# Logic_DC_Jack_v1_0.net
KiCad netlist of a schematic drawn in EAGLE
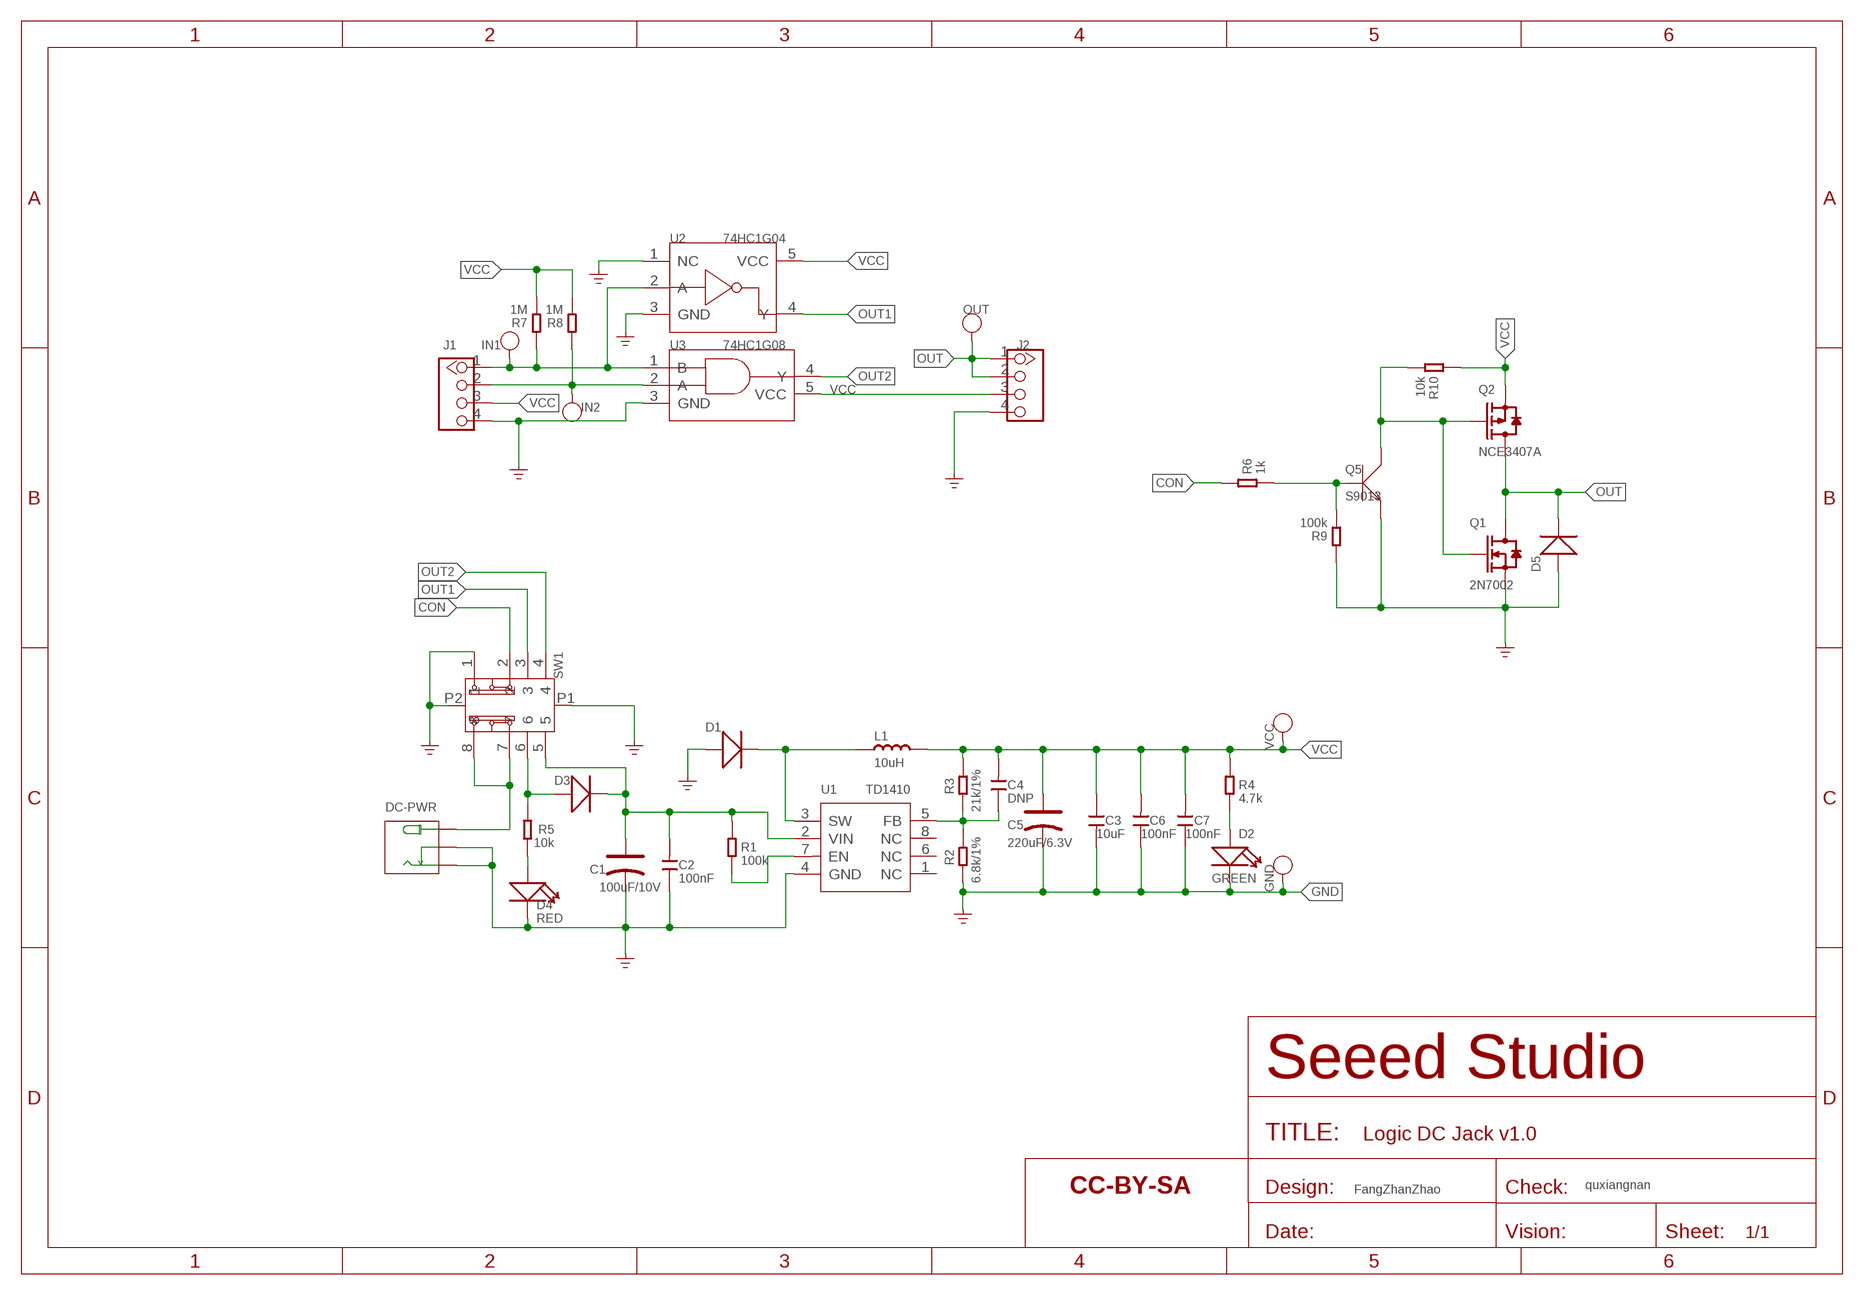
[diagram p0: schematic, sheet 1]

(export (version "E")
  (design (tool "Eeschema 10.0.6"))
  (components
    (comp (ref "C1")
      (value "100uF/10V")
      (footprint "eagle-import:AVX-B")
      (libsource (lib "eagle-import") (part "CAP-POLAR-AVX-B"))
    )
    (comp (ref "C2")
      (value "100nF")
      (footprint "eagle-import:C0603")
      (libsource (lib "eagle-import") (part "CAP-0603"))
    )
    (comp (ref "C3")
      (value "10uF")
      (footprint "eagle-import:C0805")
      (libsource (lib "eagle-import") (part "CAP-0805"))
    )
    (comp (ref "C4")
      (value "DNP")
      (footprint "eagle-import:C0603")
      (libsource (lib "eagle-import") (part "CAP-0603"))
    )
    (comp (ref "C5")
      (value "220uF/6.3V")
      (footprint "eagle-import:AVX-B")
      (libsource (lib "eagle-import") (part "CAP-POLAR-AVX-B"))
    )
    (comp (ref "C6")
      (value "100nF")
      (footprint "eagle-import:C0603")
      (libsource (lib "eagle-import") (part "CAP-0603"))
    )
    (comp (ref "C7")
      (value "100nF")
      (footprint "eagle-import:C0603")
      (libsource (lib "eagle-import") (part "CAP-0603"))
    )
    (comp (ref "D1")
      (value "DIODE'SMA'")
      (footprint "eagle-import:DO-214AC")
      (libsource (lib "eagle-import") (part "DIODE'SMA'"))
    )
    (comp (ref "D2")
      (value "GREEN")
      (footprint "eagle-import:LED-0603")
      (libsource (lib "eagle-import") (part "LED'0603'"))
    )
    (comp (ref "D3")
      (value "304020009")
      (footprint "eagle-import:DO-214AC")
      (libsource (lib "eagle-import") (part "DIODE'SMA'"))
    )
    (comp (ref "D4")
      (value "RED")
      (footprint "eagle-import:LED-0603")
      (libsource (lib "eagle-import") (part "LED'0603'"))
    )
    (comp (ref "D5")
      (value "DIODE'1206'")
      (footprint "eagle-import:SOD-123")
      (libsource (lib "eagle-import") (part "DIODE'1206'"))
    )
    (comp (ref "DC-PWR")
      (value "320120002")
      (footprint "eagle-import:3P-L11.6_W9.6_H7.0MM")
      (libsource (lib "eagle-import") (part "POWER-JACK-DC'DC-044'"))
    )
    (comp (ref "GND")
      (value "PAD-TEST-POINT'4545'")
      (footprint "eagle-import:TP-D45MIL")
      (fields (field (name "PARTNO") "DNP"))
      (libsource (lib "eagle-import") (part "PAD-TEST-POINT'4545'"))
    )
    (comp (ref "IN1")
      (value "PAD-TEST-POINT'4545'")
      (footprint "eagle-import:TP-D45MIL")
      (fields (field (name "PARTNO") "DNP"))
      (libsource (lib "eagle-import") (part "PAD-TEST-POINT'4545'"))
    )
    (comp (ref "IN2")
      (value "PAD-TEST-POINT'4545'")
      (footprint "eagle-import:TP-D45MIL")
      (fields (field (name "PARTNO") "DNP"))
      (libsource (lib "eagle-import") (part "PAD-TEST-POINT'4545'"))
    )
    (comp (ref "J1")
      (value "GROVE-CONNECTOR-DIP-2.0")
      (footprint "eagle-import:4P-2.0")
      (libsource (lib "eagle-import") (part "GROVE-CONNECTOR-DIP-2.0"))
    )
    (comp (ref "J2")
      (value "GROVE-CONNECTOR-DIP-2.0")
      (footprint "eagle-import:4P-2.0")
      (libsource (lib "eagle-import") (part "GROVE-CONNECTOR-DIP-2.0"))
    )
    (comp (ref "L1")
      (value "10uH")
      (footprint "eagle-import:L0630")
      (libsource (lib "eagle-import") (part "INDUCTOR/FERRITE-BEAD'0630'"))
    )
    (comp (ref "OUT")
      (value "PAD-TEST-POINT'4545'")
      (footprint "eagle-import:TP-D45MIL")
      (fields (field (name "PARTNO") "DNP"))
      (libsource (lib "eagle-import") (part "PAD-TEST-POINT'4545'"))
    )
    (comp (ref "Q1")
      (value "2N7002")
      (footprint "eagle-import:SOT-23")
      (libsource (lib "eagle-import") (part "MOSFET-N'SOT23'"))
    )
    (comp (ref "Q2")
      (value "NCE3407A")
      (footprint "eagle-import:SOT-23")
      (libsource (lib "eagle-import") (part "MOSFET-P'SI2323CDS/SI2305DS{lt}BR{gt}'"))
    )
    (comp (ref "Q5")
      (value "S9013")
      (footprint "eagle-import:SOT-23")
      (libsource (lib "eagle-import") (part "TRANSISTOR-NPN-SOT23"))
    )
    (comp (ref "R1")
      (value "100k")
      (footprint "eagle-import:R0603")
      (libsource (lib "eagle-import") (part "RES-0603"))
    )
    (comp (ref "R2")
      (value "6.8k/1%")
      (footprint "eagle-import:R0603")
      (libsource (lib "eagle-import") (part "RES-0603"))
    )
    (comp (ref "R3")
      (value "21k/1%")
      (footprint "eagle-import:R0603")
      (libsource (lib "eagle-import") (part "RES-0603"))
    )
    (comp (ref "R4")
      (value "4.7k")
      (footprint "eagle-import:R0603")
      (libsource (lib "eagle-import") (part "RES-0603"))
    )
    (comp (ref "R5")
      (value "10k")
      (footprint "eagle-import:R0603")
      (libsource (lib "eagle-import") (part "RES-0603"))
    )
    (comp (ref "R6")
      (value "1k")
      (footprint "eagle-import:R0603")
      (libsource (lib "eagle-import") (part "RES-0603"))
    )
    (comp (ref "R7")
      (value "1M")
      (footprint "eagle-import:R0603")
      (libsource (lib "eagle-import") (part "RES-0603"))
    )
    (comp (ref "R8")
      (value "1M")
      (footprint "eagle-import:R0603")
      (libsource (lib "eagle-import") (part "RES-0603"))
    )
    (comp (ref "R9")
      (value "100k")
      (footprint "eagle-import:R0603")
      (libsource (lib "eagle-import") (part "RES-0603"))
    )
    (comp (ref "R10")
      (value "10k")
      (footprint "eagle-import:R0603")
      (libsource (lib "eagle-import") (part "RES-0603"))
    )
    (comp (ref "SW1")
      (value "SWITCH-SK-23D07SK-22D03H-G4")
      (footprint "eagle-import:8P-3CH-L16_W6.5_H7.5MM-90D")
      (libsource (lib "eagle-import") (part "SWITCH-SK-23D07SK-22D03H-G4"))
    )
    (comp (ref "U$12")
      (value "SEEEDSTUDIO-OPEN-SCH-FRAME")
      (footprint "eagle-import:SEEEDSTUDIO-PCB-FRAME")
      (libsource (lib "eagle-import") (part "SEEEDSTUDIO-OPEN-SCH-FRAME"))
    )
    (comp (ref "U1")
      (value "TD1410")
      (footprint "eagle-import:SOP-8")
      (libsource (lib "eagle-import") (part "PMIC-TD1410"))
    )
    (comp (ref "U2")
      (value "74HC1G04")
      (footprint "eagle-import:SOT-353")
      (libsource (lib "eagle-import") (part "74HC1G04'GW'"))
    )
    (comp (ref "U3")
      (value "74HC1G08")
      (footprint "eagle-import:SOT-353")
      (libsource (lib "eagle-import") (part "74HC1G08'GW'"))
    )
    (comp (ref "VCC")
      (value "PAD-TEST-POINT'4545'")
      (footprint "eagle-import:TP-D45MIL")
      (fields (field (name "PARTNO") "DNP"))
      (libsource (lib "eagle-import") (part "PAD-TEST-POINT'4545'"))
    )
  )
  (nets
    (net (code "1") (name "CON") (class "Default")
      (node (ref "R6") (pin "2") (pinfunction "2_2") (pintype "passive"))
      (node (ref "SW1") (pin "2") (pinfunction "2_2") (pintype "bidirectional"))
    )
    (net (code "2") (name "GND") (class "Default")
      (node (ref "C1") (pin "-") (pinfunction "-_-") (pintype "passive"))
      (node (ref "C2") (pin "1") (pinfunction "1_1") (pintype "passive"))
      (node (ref "C3") (pin "2") (pinfunction "2_2") (pintype "passive"))
      (node (ref "C5") (pin "-") (pinfunction "-_-") (pintype "passive"))
      (node (ref "C6") (pin "1") (pinfunction "1_1") (pintype "passive"))
      (node (ref "C7") (pin "1") (pinfunction "1_1") (pintype "passive"))
      (node (ref "D1") (pin "1") (pinfunction "+_1") (pintype "passive"))
      (node (ref "D2") (pin "-") (pinfunction "-_-") (pintype "passive"))
      (node (ref "D4") (pin "-") (pinfunction "-_-") (pintype "passive"))
      (node (ref "D5") (pin "+") (pinfunction "+_+") (pintype "passive"))
      (node (ref "DC-PWR") (pin "-") (pinfunction "-_-") (pintype "bidirectional"))
      (node (ref "DC-PWR") (pin "CDN") (pinfunction "CDN_CDN") (pintype "bidirectional"))
      (node (ref "GND") (pin "T") (pinfunction "T_T") (pintype "bidirectional"))
      (node (ref "J1") (pin "4") (pinfunction "4_4") (pintype "bidirectional"))
      (node (ref "J2") (pin "4") (pinfunction "4_4") (pintype "bidirectional"))
      (node (ref "Q1") (pin "2") (pinfunction "S_2") (pintype "passive"))
      (node (ref "Q5") (pin "2") (pinfunction "E_2") (pintype "passive"))
      (node (ref "R2") (pin "1") (pinfunction "1_1") (pintype "passive"))
      (node (ref "R9") (pin "2") (pinfunction "2_2") (pintype "passive"))
      (node (ref "SW1") (pin "1") (pinfunction "1_1") (pintype "bidirectional"))
      (node (ref "SW1") (pin "P1") (pinfunction "P$1_P1") (pintype "bidirectional"))
      (node (ref "SW1") (pin "P2") (pinfunction "P$2_P2") (pintype "bidirectional"))
      (node (ref "U1") (pin "4") (pinfunction "GND_4") (pintype "power_in"))
      (node (ref "U2") (pin "1") (pinfunction "NC_1") (pintype "bidirectional"))
      (node (ref "U2") (pin "3") (pinfunction "GND_3") (pintype "power_in"))
      (node (ref "U3") (pin "3") (pinfunction "GND_3") (pintype "bidirectional"))
    )
    (net (code "3") (name "Net-(D1--)") (class "Default")
      (node (ref "D1") (pin "2") (pinfunction "-_2") (pintype "passive"))
      (node (ref "L1") (pin "1") (pinfunction "1_1") (pintype "passive"))
      (node (ref "U1") (pin "3") (pinfunction "SW_3") (pintype "output"))
    )
    (net (code "4") (name "Net-(D2-Pad+)") (class "Default")
      (node (ref "D2") (pin "+") (pinfunction "+_+") (pintype "passive"))
      (node (ref "R4") (pin "1") (pinfunction "1_1") (pintype "passive"))
    )
    (net (code "5") (name "Net-(D3-+)") (class "Default")
      (node (ref "D3") (pin "1") (pinfunction "+_1") (pintype "passive"))
      (node (ref "R5") (pin "2") (pinfunction "2_2") (pintype "passive"))
      (node (ref "SW1") (pin "6") (pinfunction "6_6") (pintype "bidirectional"))
    )
    (net (code "6") (name "Net-(D3--)") (class "Default")
      (node (ref "C1") (pin "+") (pinfunction "+_+") (pintype "passive"))
      (node (ref "C2") (pin "2") (pinfunction "2_2") (pintype "passive"))
      (node (ref "D3") (pin "2") (pinfunction "-_2") (pintype "passive"))
      (node (ref "R1") (pin "2") (pinfunction "2_2") (pintype "passive"))
      (node (ref "SW1") (pin "5") (pinfunction "5_5") (pintype "bidirectional"))
      (node (ref "U1") (pin "2") (pinfunction "VIN_2") (pintype "input"))
    )
    (net (code "7") (name "Net-(D4-Pad+)") (class "Default")
      (node (ref "D4") (pin "+") (pinfunction "+_+") (pintype "passive"))
      (node (ref "R5") (pin "1") (pinfunction "1_1") (pintype "passive"))
    )
    (net (code "8") (name "Net-(DC-PWR-Pad+)") (class "Default")
      (node (ref "DC-PWR") (pin "+") (pinfunction "+_+") (pintype "bidirectional"))
      (node (ref "SW1") (pin "7") (pinfunction "7_7") (pintype "bidirectional"))
      (node (ref "SW1") (pin "8") (pinfunction "8_8") (pintype "bidirectional"))
    )
    (net (code "9") (name "Net-(Q1-G)") (class "Default")
      (node (ref "Q1") (pin "1") (pinfunction "G_1") (pintype "passive"))
      (node (ref "Q2") (pin "1") (pinfunction "G_1") (pintype "passive"))
      (node (ref "Q5") (pin "3") (pinfunction "C_3") (pintype "passive"))
      (node (ref "R10") (pin "1") (pinfunction "1_1") (pintype "passive"))
    )
    (net (code "10") (name "Net-(Q5-B)") (class "Default")
      (node (ref "Q5") (pin "1") (pinfunction "B_1") (pintype "passive"))
      (node (ref "R6") (pin "1") (pinfunction "1_1") (pintype "passive"))
      (node (ref "R9") (pin "1") (pinfunction "1_1") (pintype "passive"))
    )
    (net (code "11") (name "Net-(U1-EN)") (class "Default")
      (node (ref "R1") (pin "1") (pinfunction "1_1") (pintype "passive"))
      (node (ref "U1") (pin "7") (pinfunction "EN_7") (pintype "input"))
    )
    (net (code "12") (name "Net-(U1-FB)") (class "Default")
      (node (ref "C4") (pin "1") (pinfunction "1_1") (pintype "passive"))
      (node (ref "R2") (pin "2") (pinfunction "2_2") (pintype "passive"))
      (node (ref "R3") (pin "2") (pinfunction "2_2") (pintype "passive"))
      (node (ref "U1") (pin "5") (pinfunction "FB_5") (pintype "input"))
    )
    (net (code "13") (name "Net-(U2-A)") (class "Default")
      (node (ref "IN1") (pin "T") (pinfunction "T_T") (pintype "bidirectional"))
      (node (ref "J1") (pin "1") (pinfunction "1_1") (pintype "bidirectional"))
      (node (ref "R7") (pin "2") (pinfunction "2_2") (pintype "passive"))
      (node (ref "U2") (pin "2") (pinfunction "A_2") (pintype "bidirectional"))
      (node (ref "U3") (pin "1") (pinfunction "B_1") (pintype "bidirectional"))
    )
    (net (code "14") (name "Net-(U3-A)") (class "Default")
      (node (ref "IN2") (pin "T") (pinfunction "T_T") (pintype "bidirectional"))
      (node (ref "J1") (pin "2") (pinfunction "2_2") (pintype "bidirectional"))
      (node (ref "R8") (pin "2") (pinfunction "2_2") (pintype "passive"))
      (node (ref "U3") (pin "2") (pinfunction "A_2") (pintype "bidirectional"))
    )
    (net (code "15") (name "OUT") (class "Default")
      (node (ref "D5") (pin "-") (pinfunction "-_-") (pintype "passive"))
      (node (ref "J2") (pin "1") (pinfunction "1_1") (pintype "bidirectional"))
      (node (ref "J2") (pin "2") (pinfunction "2_2") (pintype "bidirectional"))
      (node (ref "OUT") (pin "T") (pinfunction "T_T") (pintype "bidirectional"))
      (node (ref "Q1") (pin "3") (pinfunction "D_3") (pintype "passive"))
      (node (ref "Q2") (pin "3") (pinfunction "D_3") (pintype "passive"))
    )
    (net (code "16") (name "OUT1") (class "Default")
      (node (ref "SW1") (pin "3") (pinfunction "3_3") (pintype "bidirectional"))
      (node (ref "U2") (pin "4") (pinfunction "Y_4") (pintype "bidirectional"))
    )
    (net (code "17") (name "OUT2") (class "Default")
      (node (ref "SW1") (pin "4") (pinfunction "4_4") (pintype "bidirectional"))
      (node (ref "U3") (pin "4") (pinfunction "Y_4") (pintype "bidirectional"))
    )
    (net (code "18") (name "VCC") (class "Default")
      (node (ref "C3") (pin "1") (pinfunction "1_1") (pintype "passive"))
      (node (ref "C4") (pin "2") (pinfunction "2_2") (pintype "passive"))
      (node (ref "C5") (pin "+") (pinfunction "+_+") (pintype "passive"))
      (node (ref "C6") (pin "2") (pinfunction "2_2") (pintype "passive"))
      (node (ref "C7") (pin "2") (pinfunction "2_2") (pintype "passive"))
      (node (ref "J1") (pin "3") (pinfunction "3_3") (pintype "bidirectional"))
      (node (ref "J2") (pin "3") (pinfunction "3_3") (pintype "bidirectional"))
      (node (ref "L1") (pin "2") (pinfunction "2_2") (pintype "passive"))
      (node (ref "Q2") (pin "2") (pinfunction "S_2") (pintype "passive"))
      (node (ref "R10") (pin "2") (pinfunction "2_2") (pintype "passive"))
      (node (ref "R3") (pin "1") (pinfunction "1_1") (pintype "passive"))
      (node (ref "R4") (pin "2") (pinfunction "2_2") (pintype "passive"))
      (node (ref "R7") (pin "1") (pinfunction "1_1") (pintype "passive"))
      (node (ref "R8") (pin "1") (pinfunction "1_1") (pintype "passive"))
      (node (ref "U2") (pin "5") (pinfunction "VCC_5") (pintype "power_in"))
      (node (ref "U3") (pin "5") (pinfunction "VCC_5") (pintype "bidirectional"))
      (node (ref "VCC") (pin "T") (pinfunction "T_T") (pintype "bidirectional"))
    )
    (net (code "19") (name "unconnected-(U1-NC-Pad1)") (class "Default")
      (node (ref "U1") (pin "1") (pinfunction "NC_1") (pintype "no_connect"))
    )
    (net (code "20") (name "unconnected-(U1-NC-Pad6)") (class "Default")
      (node (ref "U1") (pin "6") (pinfunction "NC_6") (pintype "no_connect"))
    )
    (net (code "21") (name "unconnected-(U1-NC-Pad8)") (class "Default")
      (node (ref "U1") (pin "8") (pinfunction "NC_8") (pintype "no_connect"))
    )
  )
)
